# SCH__MainProcessor.net
KiCad netlist of a schematic drawn in Altium Designer
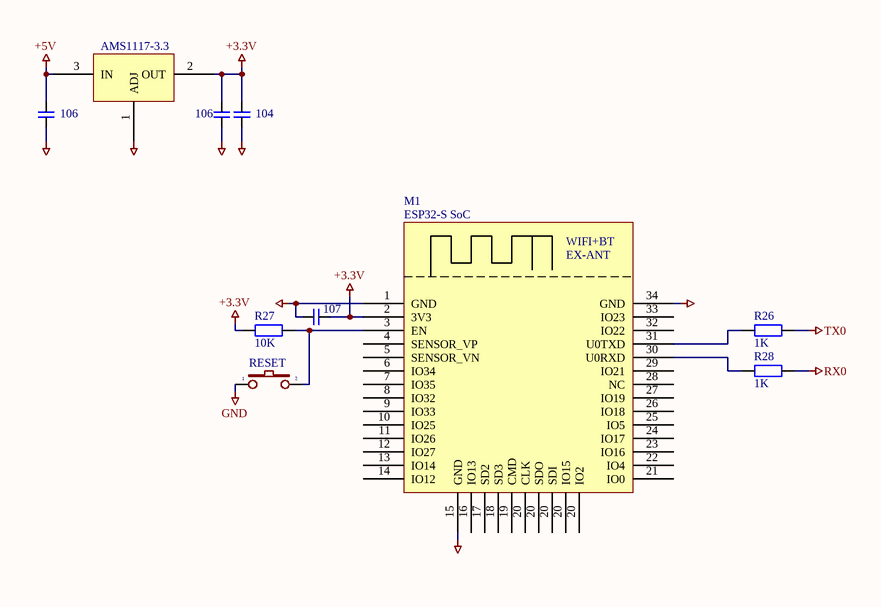
[diagram p0: [SCH]_MainProcessor.SchDoc]

(export (version "E")
  (design (tool "Eeschema 10.0.6"))
  (components
    (comp (ref "C13")
      (value "106")
      (footprint "CAP-SMD-01005")
      (description "Non-polar capacitor")
      (libsource (lib "Library") (part "Cap-Non-SMD"))
    )
    (comp (ref "C14")
      (value "106")
      (footprint "CAP-SMD-01005")
      (description "Non-polar capacitor")
      (libsource (lib "Library") (part "Cap-Non-SMD"))
    )
    (comp (ref "C15")
      (value "104")
      (footprint "CAP-SMD-01005")
      (description "Non-polar capacitor")
      (libsource (lib "Library") (part "Cap-Non-SMD"))
    )
    (comp (ref "C16")
      (value "107")
      (footprint "CAP-SMD-01005")
      (description "Non-polar capacitor")
      (libsource (lib "Library") (part "Cap-Non-SMD"))
    )
    (comp (ref "IC4")
      (value "AMS1117-3.3")
      (footprint "SOT223(123)")
      (libsource (lib "Library") (part "AMS1117"))
    )
    (comp (ref "K1")
      (value "RESET")
      (footprint "Button-SMD2/3x6")
      (description "Switch button 2 pin")
      (libsource (lib "Library") (part "Button-2"))
    )
    (comp (ref "M1")
      (value "ESP32-S SoC")
      (footprint "ESP32-S-Footprint")
      (libsource (lib "TOAN_VERSION_1_0") (part "ESP32-S WIFI_BT_SoC"))
    )
    (comp (ref "R26")
      (value "1K")
      (footprint "RES-SMD-0805")
      (description "Resistor SMD")
      (libsource (lib "Library") (part "Res SMD"))
    )
    (comp (ref "R27")
      (value "10K")
      (footprint "RES-SMD-0805")
      (description "Resistor SMD")
      (libsource (lib "Library") (part "Res SMD"))
    )
    (comp (ref "R28")
      (value "1K")
      (footprint "RES-SMD-0805")
      (description "Resistor SMD")
      (libsource (lib "Library") (part "Res SMD"))
    )
  )
  (nets
    (net (code "1") (name "+3.3V") (class "Default")
      (node (ref "C14") (pin "2") (pinfunction "2_2") (pintype "passive"))
      (node (ref "C15") (pin "2") (pinfunction "2_2") (pintype "passive"))
      (node (ref "C16") (pin "2") (pinfunction "2_2") (pintype "passive"))
      (node (ref "IC4") (pin "2") (pinfunction "OUT_2") (pintype "passive"))
      (node (ref "M1") (pin "2") (pinfunction "3V3_2") (pintype "passive"))
      (node (ref "R27") (pin "2") (pinfunction "2_2") (pintype "passive"))
    )
    (net (code "2") (name "+5V") (class "Default")
      (node (ref "C13") (pin "2") (pinfunction "2_2") (pintype "passive"))
      (node (ref "IC4") (pin "3") (pinfunction "IN_3") (pintype "passive"))
    )
    (net (code "3") (name "GND") (class "Default")
      (node (ref "C13") (pin "1") (pinfunction "1_1") (pintype "passive"))
      (node (ref "C14") (pin "1") (pinfunction "1_1") (pintype "passive"))
      (node (ref "C15") (pin "1") (pinfunction "1_1") (pintype "passive"))
      (node (ref "C16") (pin "1") (pinfunction "1_1") (pintype "passive"))
      (node (ref "IC4") (pin "1") (pinfunction "ADJ_1") (pintype "passive"))
      (node (ref "K1") (pin "1") (pinfunction "1_1") (pintype "passive"))
      (node (ref "M1") (pin "1") (pinfunction "GND_1") (pintype "passive"))
      (node (ref "M1") (pin "15") (pinfunction "GND_15") (pintype "passive"))
      (node (ref "M1") (pin "34") (pinfunction "GND_34") (pintype "passive"))
    )
    (net (code "4") (name "Net-(M1-EN)") (class "Default")
      (node (ref "K1") (pin "2") (pinfunction "2_2") (pintype "passive"))
      (node (ref "M1") (pin "3") (pinfunction "EN_3") (pintype "passive"))
      (node (ref "R27") (pin "1") (pinfunction "1_1") (pintype "passive"))
    )
    (net (code "5") (name "Net-(M1-U0RXD)") (class "Default")
      (node (ref "M1") (pin "30") (pinfunction "U0RXD_30") (pintype "passive"))
      (node (ref "R28") (pin "2") (pinfunction "2_2") (pintype "passive"))
    )
    (net (code "6") (name "Net-(M1-U0TXD)") (class "Default")
      (node (ref "M1") (pin "31") (pinfunction "U0TXD_31") (pintype "passive"))
      (node (ref "R26") (pin "2") (pinfunction "2_2") (pintype "passive"))
    )
    (net (code "7") (name "RX0") (class "Default")
      (node (ref "R28") (pin "1") (pinfunction "1_1") (pintype "passive"))
    )
    (net (code "8") (name "TX0") (class "Default")
      (node (ref "R26") (pin "1") (pinfunction "1_1") (pintype "passive"))
    )
    (net (code "9") (name "unconnected-(M1-CLK-Pad20)") (class "Default")
      (node (ref "M1") (pin "20") (pinfunction "CLK_20") (pintype "passive"))
    )
    (net (code "10") (name "unconnected-(M1-CMD-Pad19)") (class "Default")
      (node (ref "M1") (pin "19") (pinfunction "CMD_19") (pintype "passive"))
    )
    (net (code "11") (name "unconnected-(M1-IO0-Pad21)") (class "Default")
      (node (ref "M1") (pin "21") (pinfunction "IO0_21") (pintype "passive"))
    )
    (net (code "12") (name "unconnected-(M1-IO2-Pad20)") (class "Default")
      (node (ref "M1") (pin "20") (pinfunction "IO2_20") (pintype "passive"))
    )
    (net (code "13") (name "unconnected-(M1-IO4-Pad22)") (class "Default")
      (node (ref "M1") (pin "22") (pinfunction "IO4_22") (pintype "passive"))
    )
    (net (code "14") (name "unconnected-(M1-IO5-Pad25)") (class "Default")
      (node (ref "M1") (pin "25") (pinfunction "IO5_25") (pintype "passive"))
    )
    (net (code "15") (name "unconnected-(M1-IO12-Pad14)") (class "Default")
      (node (ref "M1") (pin "14") (pinfunction "IO12_14") (pintype "passive"))
    )
    (net (code "16") (name "unconnected-(M1-IO13-Pad16)") (class "Default")
      (node (ref "M1") (pin "16") (pinfunction "IO13_16") (pintype "passive"))
    )
    (net (code "17") (name "unconnected-(M1-IO14-Pad13)") (class "Default")
      (node (ref "M1") (pin "13") (pinfunction "IO14_13") (pintype "passive"))
    )
    (net (code "18") (name "unconnected-(M1-IO15-Pad20)") (class "Default")
      (node (ref "M1") (pin "20") (pinfunction "IO15_20") (pintype "passive"))
    )
    (net (code "19") (name "unconnected-(M1-IO16-Pad23)") (class "Default")
      (node (ref "M1") (pin "23") (pinfunction "IO16_23") (pintype "passive"))
    )
    (net (code "20") (name "unconnected-(M1-IO17-Pad24)") (class "Default")
      (node (ref "M1") (pin "24") (pinfunction "IO17_24") (pintype "passive"))
    )
    (net (code "21") (name "unconnected-(M1-IO18-Pad26)") (class "Default")
      (node (ref "M1") (pin "26") (pinfunction "IO18_26") (pintype "passive"))
    )
    (net (code "22") (name "unconnected-(M1-IO19-Pad27)") (class "Default")
      (node (ref "M1") (pin "27") (pinfunction "IO19_27") (pintype "passive"))
    )
    (net (code "23") (name "unconnected-(M1-IO21-Pad29)") (class "Default")
      (node (ref "M1") (pin "29") (pinfunction "IO21_29") (pintype "passive"))
    )
    (net (code "24") (name "unconnected-(M1-IO22-Pad32)") (class "Default")
      (node (ref "M1") (pin "32") (pinfunction "IO22_32") (pintype "passive"))
    )
    (net (code "25") (name "unconnected-(M1-IO23-Pad33)") (class "Default")
      (node (ref "M1") (pin "33") (pinfunction "IO23_33") (pintype "passive"))
    )
    (net (code "26") (name "unconnected-(M1-IO25-Pad10)") (class "Default")
      (node (ref "M1") (pin "10") (pinfunction "IO25_10") (pintype "passive"))
    )
    (net (code "27") (name "unconnected-(M1-IO26-Pad11)") (class "Default")
      (node (ref "M1") (pin "11") (pinfunction "IO26_11") (pintype "passive"))
    )
    (net (code "28") (name "unconnected-(M1-IO27-Pad12)") (class "Default")
      (node (ref "M1") (pin "12") (pinfunction "IO27_12") (pintype "passive"))
    )
    (net (code "29") (name "unconnected-(M1-IO32-Pad8)") (class "Default")
      (node (ref "M1") (pin "8") (pinfunction "IO32_8") (pintype "passive"))
    )
    (net (code "30") (name "unconnected-(M1-IO33-Pad9)") (class "Default")
      (node (ref "M1") (pin "9") (pinfunction "IO33_9") (pintype "passive"))
    )
    (net (code "31") (name "unconnected-(M1-IO34-Pad6)") (class "Default")
      (node (ref "M1") (pin "6") (pinfunction "IO34_6") (pintype "passive"))
    )
    (net (code "32") (name "unconnected-(M1-IO35-Pad7)") (class "Default")
      (node (ref "M1") (pin "7") (pinfunction "IO35_7") (pintype "passive"))
    )
    (net (code "33") (name "unconnected-(M1-NC-Pad28)") (class "Default")
      (node (ref "M1") (pin "28") (pinfunction "NC_28") (pintype "passive"))
    )
    (net (code "34") (name "unconnected-(M1-SD2-Pad17)") (class "Default")
      (node (ref "M1") (pin "17") (pinfunction "SD2_17") (pintype "passive"))
    )
    (net (code "35") (name "unconnected-(M1-SD3-Pad18)") (class "Default")
      (node (ref "M1") (pin "18") (pinfunction "SD3_18") (pintype "passive"))
    )
    (net (code "36") (name "unconnected-(M1-SDI-Pad20)") (class "Default")
      (node (ref "M1") (pin "20") (pinfunction "SDI_20") (pintype "passive"))
    )
    (net (code "37") (name "unconnected-(M1-SDO-Pad20)") (class "Default")
      (node (ref "M1") (pin "20") (pinfunction "SDO_20") (pintype "passive"))
    )
    (net (code "38") (name "unconnected-(M1-SENSOR_VN-Pad5)") (class "Default")
      (node (ref "M1") (pin "5") (pinfunction "SENSOR_VN_5") (pintype "passive"))
    )
    (net (code "39") (name "unconnected-(M1-SENSOR_VP-Pad4)") (class "Default")
      (node (ref "M1") (pin "4") (pinfunction "SENSOR_VP_4") (pintype "passive"))
    )
  )
)
